# Indicadores.net
KiCad netlist of a schematic drawn in Altium Designer
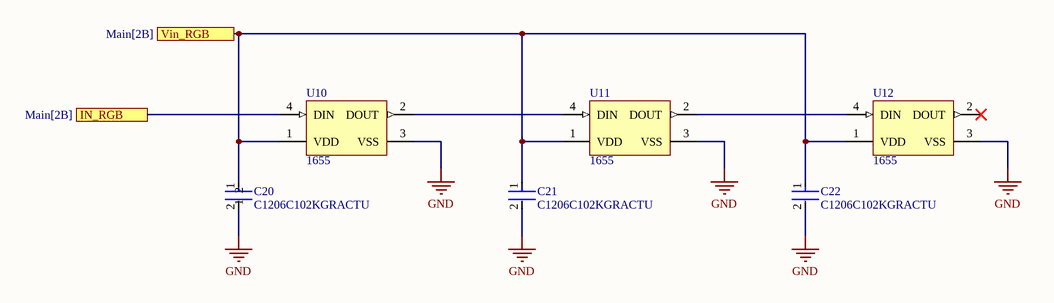
[diagram p0: Indicadores.SchDoc]

(export (version "E")
  (design (tool "Eeschema 10.0.6"))
  (components
    (comp (ref "C20")
      (value "C1206C102KGRACTU")
      (footprint "FP-C1206C-EF-IPC_A")
      (description "CAP CER 1000PF 2KV X7R 1206")
      (fields (field (name "VOLTAGE") "2kV") (field (name "TOLERANCE") "10%"))
      (libsource (lib "") (part "b4654b650e69147ec39a6b967a45e02_1"))
    )
    (comp (ref "C21")
      (value "C1206C102KGRACTU")
      (footprint "FP-C1206C-EF-IPC_A")
      (description "CAP CER 1000PF 2KV X7R 1206")
      (fields (field (name "VOLTAGE") "2kV") (field (name "TOLERANCE") "10%"))
      (libsource (lib "Altium Content Vault") (part "b4654b650e69147ec39a6b967a45e02"))
    )
    (comp (ref "C22")
      (value "C1206C102KGRACTU")
      (footprint "FP-C1206C-EF-IPC_A")
      (description "CAP CER 1000PF 2KV X7R 1206")
      (fields (field (name "VOLTAGE") "2kV") (field (name "TOLERANCE") "10%"))
      (libsource (lib "Altium Content Vault") (part "b4654b650e69147ec39a6b967a45e02"))
    )
    (comp (ref "U10")
      (value "1655")
      (footprint "ADA-RGB-1655_V")
      (fields (field (name "MANUFACTURER") "Adafruit-Industries-LLC"))
      (libsource (lib "Altium Content Vault") (part "ADA-RGB-1655-4"))
    )
    (comp (ref "U11")
      (value "1655")
      (footprint "ADA-RGB-1655_V")
      (fields (field (name "MANUFACTURER") "Adafruit-Industries-LLC"))
      (libsource (lib "Altium Content Vault") (part "ADA-RGB-1655-4"))
    )
    (comp (ref "U12")
      (value "1655")
      (footprint "ADA-RGB-1655_V")
      (fields (field (name "MANUFACTURER") "Adafruit-Industries-LLC"))
      (libsource (lib "Altium Content Vault") (part "ADA-RGB-1655-4"))
    )
  )
  (nets
    (net (code "1") (name "/IN_RGB") (class "Default")
      (node (ref "U10") (pin "4") (pinfunction "DIN_4") (pintype "input"))
    )
    (net (code "2") (name "/Vin_RGB") (class "Default")
      (node (ref "C20") (pin "1") (pinfunction "1_1") (pintype "passive"))
      (node (ref "C21") (pin "1") (pinfunction "1_1") (pintype "passive"))
      (node (ref "C22") (pin "1") (pinfunction "1_1") (pintype "passive"))
      (node (ref "U10") (pin "1") (pinfunction "VDD_1") (pintype "power_in"))
      (node (ref "U11") (pin "1") (pinfunction "VDD_1") (pintype "power_in"))
      (node (ref "U12") (pin "1") (pinfunction "VDD_1") (pintype "power_in"))
    )
    (net (code "3") (name "GND") (class "Default")
      (node (ref "C20") (pin "2") (pinfunction "2_2") (pintype "passive"))
      (node (ref "C21") (pin "2") (pinfunction "2_2") (pintype "passive"))
      (node (ref "C22") (pin "2") (pinfunction "2_2") (pintype "passive"))
      (node (ref "U10") (pin "3") (pinfunction "VSS_3") (pintype "power_in"))
      (node (ref "U11") (pin "3") (pinfunction "VSS_3") (pintype "power_in"))
      (node (ref "U12") (pin "3") (pinfunction "VSS_3") (pintype "power_in"))
    )
    (net (code "4") (name "Net-(U10-DOUT)") (class "Default")
      (node (ref "U10") (pin "2") (pinfunction "DOUT_2") (pintype "output"))
      (node (ref "U11") (pin "4") (pinfunction "DIN_4") (pintype "input"))
    )
    (net (code "5") (name "Net-(U11-DOUT)") (class "Default")
      (node (ref "U11") (pin "2") (pinfunction "DOUT_2") (pintype "output"))
      (node (ref "U12") (pin "4") (pinfunction "DIN_4") (pintype "input"))
    )
    (net (code "6") (name "unconnected-(U12-DOUT-Pad2)") (class "Default")
      (node (ref "U12") (pin "2") (pinfunction "DOUT_2") (pintype "output+no_connect"))
    )
  )
)
